# Schematic.net
KiCad netlist of a schematic drawn in EAGLE
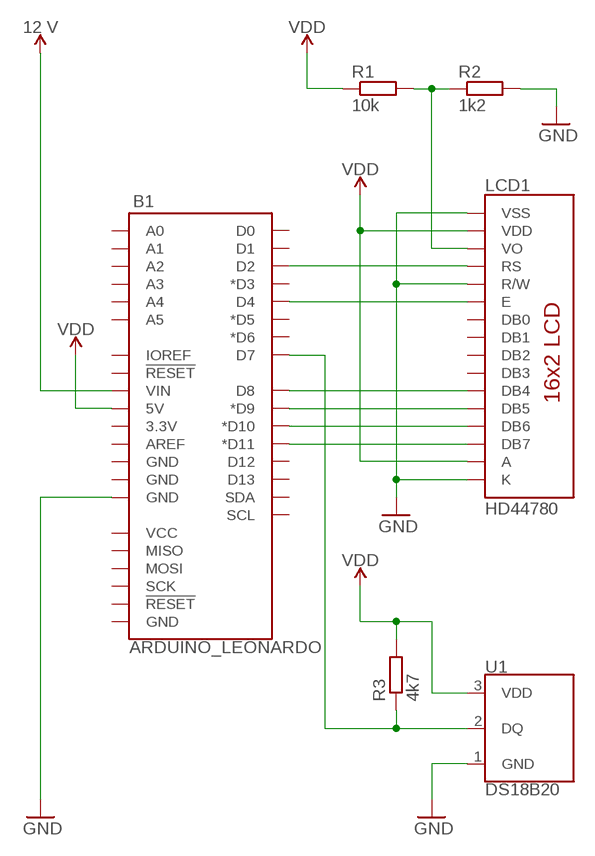
[diagram p0: schematic, sheet 1]

(export (version "E")
  (design (tool "Eeschema 10.0.6"))
  (components
    (comp (ref "B1")
      (value "ARDUINO_LEONARDO")
      (footprint "eagle-import:ARDUINO_R3")
      (libsource (lib "eagle-import") (part "ARDUINO_UNO_R3"))
    )
    (comp (ref "LCD1")
      (value "HD44780")
      (footprint "eagle-import:LCD-16X2_NOSILK")
      (libsource (lib "eagle-import") (part "LCD-16X2NOSILK"))
    )
    (comp (ref "R1")
      (value "10k")
      (footprint "eagle-import:0204_7")
      (libsource (lib "eagle-import") (part "R-EU_0204/7"))
    )
    (comp (ref "R2")
      (value "1k2")
      (footprint "eagle-import:0204_7")
      (libsource (lib "eagle-import") (part "R-EU_0204/7"))
    )
    (comp (ref "R3")
      (value "4k7")
      (footprint "eagle-import:0204_7")
      (libsource (lib "eagle-import") (part "R-EU_0204/7"))
    )
    (comp (ref "U1")
      (value "DS18B20")
      (footprint "eagle-import:TO-92-AMMO")
      (libsource (lib "eagle-import") (part "DS18B20"))
    )
  )
  (nets
    (net (code "1") (name "12 V") (class "Default")
      (node (ref "B1") (pin "5V") (pinfunction "5V_5V") (pintype "bidirectional"))
      (node (ref "B1") (pin "VIN") (pinfunction "VIN_VIN") (pintype "bidirectional"))
      (node (ref "LCD1") (pin "15") (pinfunction "A_15") (pintype "power_in"))
      (node (ref "LCD1") (pin "2") (pinfunction "VDD_2") (pintype "power_in"))
      (node (ref "R1") (pin "1") (pinfunction "1_1") (pintype "passive"))
      (node (ref "R3") (pin "2") (pinfunction "2_2") (pintype "passive"))
      (node (ref "U1") (pin "3") (pinfunction "VDD_3") (pintype "power_in"))
    )
    (net (code "2") (name "GND") (class "Default")
      (node (ref "B1") (pin "GND@2") (pinfunction "GND_GND@2") (pintype "bidirectional"))
      (node (ref "LCD1") (pin "1") (pinfunction "VSS_1") (pintype "power_in"))
      (node (ref "LCD1") (pin "16") (pinfunction "K_16") (pintype "power_in"))
      (node (ref "LCD1") (pin "5") (pinfunction "R/W_5") (pintype "input"))
      (node (ref "R2") (pin "2") (pinfunction "2_2") (pintype "passive"))
      (node (ref "U1") (pin "1") (pinfunction "GND_1") (pintype "power_in"))
    )
    (net (code "3") (name "Net-(B1-*D9)") (class "Default")
      (node (ref "B1") (pin "D9") (pinfunction "*D9_D9") (pintype "bidirectional"))
      (node (ref "LCD1") (pin "12") (pinfunction "DB5_12") (pintype "bidirectional"))
    )
    (net (code "4") (name "Net-(B1-*D10)") (class "Default")
      (node (ref "B1") (pin "D10") (pinfunction "*D10_D10") (pintype "bidirectional"))
      (node (ref "LCD1") (pin "13") (pinfunction "DB6_13") (pintype "bidirectional"))
    )
    (net (code "5") (name "Net-(B1-*D11)") (class "Default")
      (node (ref "B1") (pin "D11") (pinfunction "*D11_D11") (pintype "bidirectional"))
      (node (ref "LCD1") (pin "14") (pinfunction "DB7_14") (pintype "bidirectional"))
    )
    (net (code "6") (name "Net-(LCD1-DB4)") (class "Default")
      (node (ref "B1") (pin "D8") (pinfunction "D8_D8") (pintype "bidirectional"))
      (node (ref "LCD1") (pin "11") (pinfunction "DB4_11") (pintype "bidirectional"))
    )
    (net (code "7") (name "Net-(LCD1-E)") (class "Default")
      (node (ref "B1") (pin "D4") (pinfunction "D4_D4") (pintype "bidirectional"))
      (node (ref "LCD1") (pin "6") (pinfunction "E_6") (pintype "input"))
    )
    (net (code "8") (name "Net-(LCD1-RS)") (class "Default")
      (node (ref "B1") (pin "D2") (pinfunction "D2_D2") (pintype "bidirectional"))
      (node (ref "LCD1") (pin "4") (pinfunction "RS_4") (pintype "input"))
    )
    (net (code "9") (name "Net-(LCD1-VO)") (class "Default")
      (node (ref "LCD1") (pin "3") (pinfunction "VO_3") (pintype "bidirectional"))
      (node (ref "R1") (pin "2") (pinfunction "2_2") (pintype "passive"))
      (node (ref "R2") (pin "1") (pinfunction "1_1") (pintype "passive"))
    )
    (net (code "10") (name "Net-(U1-DQ)") (class "Default")
      (node (ref "B1") (pin "D7") (pinfunction "D7_D7") (pintype "bidirectional"))
      (node (ref "R3") (pin "1") (pinfunction "1_1") (pintype "passive"))
      (node (ref "U1") (pin "2") (pinfunction "DQ_2") (pintype "bidirectional"))
    )
    (net (code "11") (name "unconnected-(B1-*D3-PadD3)") (class "Default")
      (node (ref "B1") (pin "D3") (pinfunction "*D3_D3") (pintype "bidirectional"))
    )
    (net (code "12") (name "unconnected-(B1-*D5-PadD5)") (class "Default")
      (node (ref "B1") (pin "D5") (pinfunction "*D5_D5") (pintype "bidirectional"))
    )
    (net (code "13") (name "unconnected-(B1-*D6-PadD6)") (class "Default")
      (node (ref "B1") (pin "D6") (pinfunction "*D6_D6") (pintype "bidirectional"))
    )
    (net (code "14") (name "unconnected-(B1-GND-PadGND@1)") (class "Default")
      (node (ref "B1") (pin "GND@1") (pinfunction "GND_GND@1") (pintype "bidirectional"))
    )
    (net (code "15") (name "unconnected-(B1-GND-PadGND@3)") (class "Default")
      (node (ref "B1") (pin "GND@3") (pinfunction "GND_GND@3") (pintype "bidirectional"))
    )
    (net (code "16") (name "unconnected-(B1-GND-PadGND@4)") (class "Default")
      (node (ref "B1") (pin "GND@4") (pinfunction "GND_GND@4") (pintype "bidirectional"))
    )
    (net (code "17") (name "unconnected-(B1-Pad3.3V)") (class "Default")
      (node (ref "B1") (pin "3.3V") (pinfunction "3.3V_3.3V") (pintype "bidirectional"))
    )
    (net (code "18") (name "unconnected-(B1-PadA0)") (class "Default")
      (node (ref "B1") (pin "A0") (pinfunction "A0_A0") (pintype "bidirectional"))
    )
    (net (code "19") (name "unconnected-(B1-PadA1)") (class "Default")
      (node (ref "B1") (pin "A1") (pinfunction "A1_A1") (pintype "bidirectional"))
    )
    (net (code "20") (name "unconnected-(B1-PadA2)") (class "Default")
      (node (ref "B1") (pin "A2") (pinfunction "A2_A2") (pintype "bidirectional"))
    )
    (net (code "21") (name "unconnected-(B1-PadA3)") (class "Default")
      (node (ref "B1") (pin "A3") (pinfunction "A3_A3") (pintype "bidirectional"))
    )
    (net (code "22") (name "unconnected-(B1-PadA4)") (class "Default")
      (node (ref "B1") (pin "A4") (pinfunction "A4_A4") (pintype "bidirectional"))
    )
    (net (code "23") (name "unconnected-(B1-PadA5)") (class "Default")
      (node (ref "B1") (pin "A5") (pinfunction "A5_A5") (pintype "bidirectional"))
    )
    (net (code "24") (name "unconnected-(B1-PadAREF)") (class "Default")
      (node (ref "B1") (pin "AREF") (pinfunction "AREF_AREF") (pintype "bidirectional"))
    )
    (net (code "25") (name "unconnected-(B1-PadD0)") (class "Default")
      (node (ref "B1") (pin "D0") (pinfunction "D0_D0") (pintype "bidirectional"))
    )
    (net (code "26") (name "unconnected-(B1-PadD1)") (class "Default")
      (node (ref "B1") (pin "D1") (pinfunction "D1_D1") (pintype "bidirectional"))
    )
    (net (code "27") (name "unconnected-(B1-PadD12)") (class "Default")
      (node (ref "B1") (pin "D12") (pinfunction "D12_D12") (pintype "bidirectional"))
    )
    (net (code "28") (name "unconnected-(B1-PadD13)") (class "Default")
      (node (ref "B1") (pin "D13") (pinfunction "D13_D13") (pintype "bidirectional"))
    )
    (net (code "29") (name "unconnected-(B1-PadIOREF)") (class "Default")
      (node (ref "B1") (pin "IOREF") (pinfunction "IOREF_IOREF") (pintype "bidirectional"))
    )
    (net (code "30") (name "unconnected-(B1-PadMISO)") (class "Default")
      (node (ref "B1") (pin "MISO") (pinfunction "MISO_MISO") (pintype "bidirectional"))
    )
    (net (code "31") (name "unconnected-(B1-PadMOSI)") (class "Default")
      (node (ref "B1") (pin "MOSI") (pinfunction "MOSI_MOSI") (pintype "bidirectional"))
    )
    (net (code "32") (name "unconnected-(B1-PadSCK)") (class "Default")
      (node (ref "B1") (pin "SCK") (pinfunction "SCK_SCK") (pintype "bidirectional"))
    )
    (net (code "33") (name "unconnected-(B1-PadSCL)") (class "Default")
      (node (ref "B1") (pin "SCL") (pinfunction "SCL_SCL") (pintype "bidirectional"))
    )
    (net (code "34") (name "unconnected-(B1-PadSDA)") (class "Default")
      (node (ref "B1") (pin "SDA") (pinfunction "SDA_SDA") (pintype "bidirectional"))
    )
    (net (code "35") (name "unconnected-(B1-PadVCC)") (class "Default")
      (node (ref "B1") (pin "VCC") (pinfunction "VCC_VCC") (pintype "bidirectional"))
    )
    (net (code "36") (name "unconnected-(B1-~{RESET}-PadRESET@1)") (class "Default")
      (node (ref "B1") (pin "RESET@1") (pinfunction "~{RESET}_RESET@1") (pintype "bidirectional"))
    )
    (net (code "37") (name "unconnected-(B1-~{RESET}-PadRESET@2)") (class "Default")
      (node (ref "B1") (pin "RESET@2") (pinfunction "~{RESET}_RESET@2") (pintype "bidirectional"))
    )
    (net (code "38") (name "unconnected-(LCD1-DB0-Pad7)") (class "Default")
      (node (ref "LCD1") (pin "7") (pinfunction "DB0_7") (pintype "bidirectional"))
    )
    (net (code "39") (name "unconnected-(LCD1-DB1-Pad8)") (class "Default")
      (node (ref "LCD1") (pin "8") (pinfunction "DB1_8") (pintype "bidirectional"))
    )
    (net (code "40") (name "unconnected-(LCD1-DB2-Pad9)") (class "Default")
      (node (ref "LCD1") (pin "9") (pinfunction "DB2_9") (pintype "bidirectional"))
    )
    (net (code "41") (name "unconnected-(LCD1-DB3-Pad10)") (class "Default")
      (node (ref "LCD1") (pin "10") (pinfunction "DB3_10") (pintype "bidirectional"))
    )
  )
)
